# THAT340.net
KiCad netlist of a schematic drawn in EAGLE
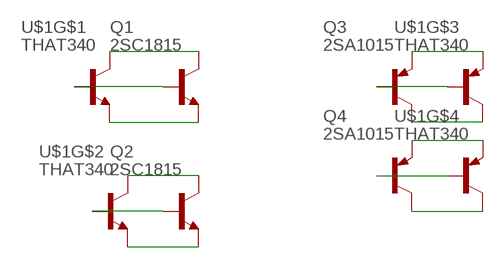
[diagram p0: schematic, sheet 1]

(export (version "E")
  (design (tool "Eeschema 10.0.6"))
  (components
    (comp (ref "Q1")
      (value "2SC1815")
      (footprint "eagle-import:TO92-BCE")
      (libsource (lib "eagle-import") (part "2SC1815"))
    )
    (comp (ref "Q2")
      (value "2SC1815")
      (footprint "eagle-import:TO92-BCE")
      (libsource (lib "eagle-import") (part "2SC1815"))
    )
    (comp (ref "Q3")
      (value "2SA1015")
      (footprint "eagle-import:TO92-BCE")
      (libsource (lib "eagle-import") (part "2SA1015"))
    )
    (comp (ref "Q4")
      (value "2SA1015")
      (footprint "eagle-import:TO92-BCE")
      (libsource (lib "eagle-import") (part "2SA1015"))
    )
    (comp (ref "U$1")
      (value "THAT340")
      (footprint "eagle-import:DIP254P762X510-14")
      (libsource (lib "eagle-import") (part "THAT340"))
    )
  )
  (nets
    (net (code "1") (name "Net-(U$1A-B)") (class "Default")
      (node (ref "Q1") (pin "B") (pinfunction "B_B") (pintype "passive"))
      (node (ref "U$1") (pin "2") (pinfunction "B_2") (pintype "passive"))
    )
    (net (code "2") (name "Net-(U$1A-C)") (class "Default")
      (node (ref "Q1") (pin "C") (pinfunction "C_C") (pintype "passive"))
      (node (ref "U$1") (pin "1") (pinfunction "C_1") (pintype "passive"))
    )
    (net (code "3") (name "Net-(U$1A-E)") (class "Default")
      (node (ref "Q1") (pin "E") (pinfunction "E_E") (pintype "passive"))
      (node (ref "U$1") (pin "3") (pinfunction "E_3") (pintype "passive"))
    )
    (net (code "4") (name "Net-(U$1B-B)") (class "Default")
      (node (ref "Q2") (pin "B") (pinfunction "B_B") (pintype "passive"))
      (node (ref "U$1") (pin "13") (pinfunction "B_13") (pintype "passive"))
    )
    (net (code "5") (name "Net-(U$1B-C)") (class "Default")
      (node (ref "Q2") (pin "C") (pinfunction "C_C") (pintype "passive"))
      (node (ref "U$1") (pin "14") (pinfunction "C_14") (pintype "passive"))
    )
    (net (code "6") (name "Net-(U$1B-E)") (class "Default")
      (node (ref "Q2") (pin "E") (pinfunction "E_E") (pintype "passive"))
      (node (ref "U$1") (pin "12") (pinfunction "E_12") (pintype "passive"))
    )
    (net (code "7") (name "Net-(U$1C-B)") (class "Default")
      (node (ref "Q3") (pin "B") (pinfunction "B_B") (pintype "passive"))
      (node (ref "U$1") (pin "6") (pinfunction "B_6") (pintype "passive"))
    )
    (net (code "8") (name "Net-(U$1C-C)") (class "Default")
      (node (ref "Q3") (pin "C") (pinfunction "C_C") (pintype "passive"))
      (node (ref "U$1") (pin "7") (pinfunction "C_7") (pintype "passive"))
    )
    (net (code "9") (name "Net-(U$1C-E)") (class "Default")
      (node (ref "Q3") (pin "E") (pinfunction "E_E") (pintype "passive"))
      (node (ref "U$1") (pin "5") (pinfunction "E_5") (pintype "passive"))
    )
    (net (code "10") (name "Net-(U$1D-B)") (class "Default")
      (node (ref "Q4") (pin "B") (pinfunction "B_B") (pintype "passive"))
      (node (ref "U$1") (pin "9") (pinfunction "B_9") (pintype "passive"))
    )
    (net (code "11") (name "Net-(U$1D-C)") (class "Default")
      (node (ref "Q4") (pin "C") (pinfunction "C_C") (pintype "passive"))
      (node (ref "U$1") (pin "8") (pinfunction "C_8") (pintype "passive"))
    )
    (net (code "12") (name "Net-(U$1D-E)") (class "Default")
      (node (ref "Q4") (pin "E") (pinfunction "E_E") (pintype "passive"))
      (node (ref "U$1") (pin "10") (pinfunction "E_10") (pintype "passive"))
    )
  )
)
